# reflectionSensor.net
KiCad netlist of a schematic drawn in EAGLE
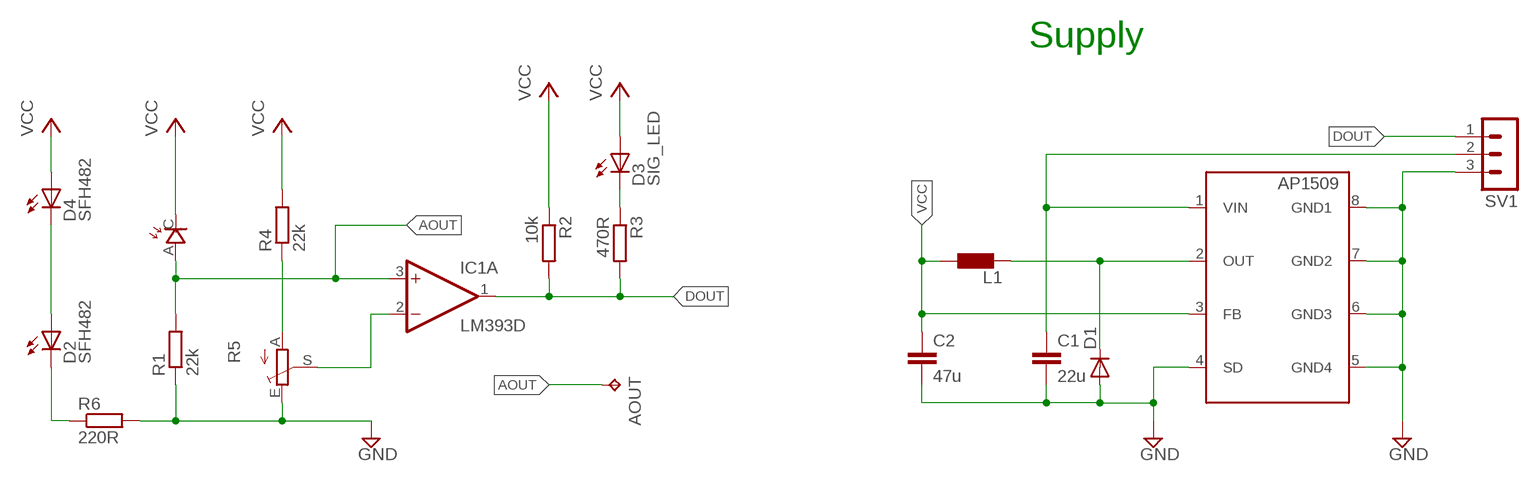
[diagram p0: schematic, sheet 1]

(export (version "E")
  (design (tool "Eeschema 10.0.6"))
  (components
    (comp (ref "AOUT")
      (value "TPTP20SQ")
      (footprint "eagle-import:TP20SQ")
      (libsource (lib "eagle-import") (part "TPTP20SQ"))
    )
    (comp (ref "C1")
      (value "22u")
      (footprint "eagle-import:C1210")
      (libsource (lib "eagle-import") (part "C-EUC1210"))
    )
    (comp (ref "C2")
      (value "47u")
      (footprint "eagle-import:C1210")
      (libsource (lib "eagle-import") (part "C-EUC1210"))
    )
    (comp (ref "D1")
      (value "DIODE-SOD323-W")
      (footprint "eagle-import:SOD323-W")
      (libsource (lib "eagle-import") (part "DIODE-SOD323-W"))
    )
    (comp (ref "D2")
      (value "SFH482")
      (footprint "eagle-import:SFH482")
      (libsource (lib "eagle-import") (part "SFH482"))
    )
    (comp (ref "D3")
      (value "SIG_LED")
      (footprint "eagle-import:SFH482")
      (libsource (lib "eagle-import") (part "SFH482"))
    )
    (comp (ref "D4")
      (value "SFH482")
      (footprint "eagle-import:SFH482")
      (libsource (lib "eagle-import") (part "SFH482"))
    )
    (comp (ref "IC1")
      (value "LM393D")
      (footprint "eagle-import:SO08")
      (libsource (lib "eagle-import") (part "LM393D"))
    )
    (comp (ref "L1")
      (value "LL5650M")
      (footprint "eagle-import:L5650M")
      (libsource (lib "eagle-import") (part "LL5650M"))
    )
    (comp (ref "R1")
      (value "22k")
      (footprint "eagle-import:M1206")
      (libsource (lib "eagle-import") (part "resistor_348_R-EU_M1206"))
    )
    (comp (ref "R2")
      (value "10k")
      (footprint "eagle-import:M0805")
      (libsource (lib "eagle-import") (part "R-EU_M0805"))
    )
    (comp (ref "R3")
      (value "470R")
      (footprint "eagle-import:M0805")
      (libsource (lib "eagle-import") (part "R-EU_M0805"))
    )
    (comp (ref "R4")
      (value "22k")
      (footprint "eagle-import:M1206")
      (libsource (lib "eagle-import") (part "resistor_348_R-EU_M1206"))
    )
    (comp (ref "R5")
      (value "TRIM_EU-CA9V")
      (footprint "eagle-import:CA9V")
      (libsource (lib "eagle-import") (part "TRIM_EU-CA9V"))
    )
    (comp (ref "R6")
      (value "220R")
      (footprint "eagle-import:M1206")
      (libsource (lib "eagle-import") (part "resistor_348_R-EU_M1206"))
    )
    (comp (ref "SV1")
      (value "MA03-1")
      (footprint "eagle-import:MA03-1")
      (libsource (lib "eagle-import") (part "MA03-1"))
    )
    (comp (ref "U$1")
      (value "AP1509")
      (footprint "eagle-import:SOP08")
      (libsource (lib "eagle-import") (part "AP1509"))
    )
    (comp (ref "U$2")
      (value "PHOTODIODE")
      (footprint "eagle-import:PHOTODIODE")
      (libsource (lib "eagle-import") (part "PHOTODIODE"))
    )
  )
  (nets
    (net (code "1") (name "AOUT") (class "Default")
      (node (ref "AOUT") (pin "TP") (pinfunction "TP_TP") (pintype "input"))
      (node (ref "IC1") (pin "3") (pinfunction "+IN_3") (pintype "input"))
      (node (ref "R1") (pin "2") (pinfunction "2_2") (pintype "passive"))
      (node (ref "U$2") (pin "A") (pinfunction "A_A") (pintype "bidirectional"))
    )
    (net (code "2") (name "DOUT") (class "Default")
      (node (ref "IC1") (pin "1") (pinfunction "OUT_1") (pintype "output"))
      (node (ref "R2") (pin "2") (pinfunction "2_2") (pintype "passive"))
      (node (ref "R3") (pin "2") (pinfunction "2_2") (pintype "passive"))
      (node (ref "SV1") (pin "1") (pinfunction "1_1") (pintype "passive"))
    )
    (net (code "3") (name "GND") (class "Default")
      (node (ref "C1") (pin "2") (pinfunction "2_2") (pintype "passive"))
      (node (ref "C2") (pin "2") (pinfunction "2_2") (pintype "passive"))
      (node (ref "D1") (pin "A") (pinfunction "A_A") (pintype "passive"))
      (node (ref "R1") (pin "1") (pinfunction "1_1") (pintype "passive"))
      (node (ref "R5") (pin "E") (pinfunction "E_E") (pintype "passive"))
      (node (ref "R6") (pin "2") (pinfunction "2_2") (pintype "passive"))
      (node (ref "SV1") (pin "3") (pinfunction "3_3") (pintype "passive"))
      (node (ref "U$1") (pin "4") (pinfunction "SD_4") (pintype "bidirectional"))
      (node (ref "U$1") (pin "5") (pinfunction "GND4_5") (pintype "bidirectional"))
      (node (ref "U$1") (pin "6") (pinfunction "GND3_6") (pintype "bidirectional"))
      (node (ref "U$1") (pin "7") (pinfunction "GND2_7") (pintype "bidirectional"))
      (node (ref "U$1") (pin "8") (pinfunction "GND1_8") (pintype "bidirectional"))
    )
    (net (code "4") (name "Net-(D2-C)") (class "Default")
      (node (ref "D2") (pin "K") (pinfunction "C_K") (pintype "passive"))
      (node (ref "R6") (pin "1") (pinfunction "1_1") (pintype "passive"))
    )
    (net (code "5") (name "Net-(D3-C)") (class "Default")
      (node (ref "D3") (pin "K") (pinfunction "C_K") (pintype "passive"))
      (node (ref "R3") (pin "1") (pinfunction "1_1") (pintype "passive"))
    )
    (net (code "6") (name "Net-(D4-C)") (class "Default")
      (node (ref "D2") (pin "A") (pinfunction "A_A") (pintype "passive"))
      (node (ref "D4") (pin "K") (pinfunction "C_K") (pintype "passive"))
    )
    (net (code "7") (name "Net-(IC1A--IN)") (class "Default")
      (node (ref "IC1") (pin "2") (pinfunction "-IN_2") (pintype "input"))
      (node (ref "R5") (pin "S") (pinfunction "S_S") (pintype "passive"))
    )
    (net (code "8") (name "Net-(R4-Pad1)") (class "Default")
      (node (ref "R4") (pin "1") (pinfunction "1_1") (pintype "passive"))
      (node (ref "R5") (pin "A") (pinfunction "A_A") (pintype "passive"))
    )
    (net (code "9") (name "Net-(U$1-OUT)") (class "Default")
      (node (ref "D1") (pin "C") (pinfunction "C_C") (pintype "passive"))
      (node (ref "L1") (pin "2") (pinfunction "2_2") (pintype "passive"))
      (node (ref "U$1") (pin "2") (pinfunction "OUT_2") (pintype "bidirectional"))
    )
    (net (code "10") (name "Net-(U$1-VIN)") (class "Default")
      (node (ref "C1") (pin "1") (pinfunction "1_1") (pintype "passive"))
      (node (ref "SV1") (pin "2") (pinfunction "2_2") (pintype "passive"))
      (node (ref "U$1") (pin "1") (pinfunction "VIN_1") (pintype "bidirectional"))
    )
    (net (code "11") (name "VCC") (class "Default")
      (node (ref "C2") (pin "1") (pinfunction "1_1") (pintype "passive"))
      (node (ref "D3") (pin "A") (pinfunction "A_A") (pintype "passive"))
      (node (ref "D4") (pin "A") (pinfunction "A_A") (pintype "passive"))
      (node (ref "L1") (pin "1") (pinfunction "1_1") (pintype "passive"))
      (node (ref "R2") (pin "1") (pinfunction "1_1") (pintype "passive"))
      (node (ref "R4") (pin "2") (pinfunction "2_2") (pintype "passive"))
      (node (ref "U$1") (pin "3") (pinfunction "FB_3") (pintype "bidirectional"))
      (node (ref "U$2") (pin "C") (pinfunction "C_C") (pintype "bidirectional"))
    )
  )
)
